# main.net
KiCad netlist of a schematic drawn in EAGLE
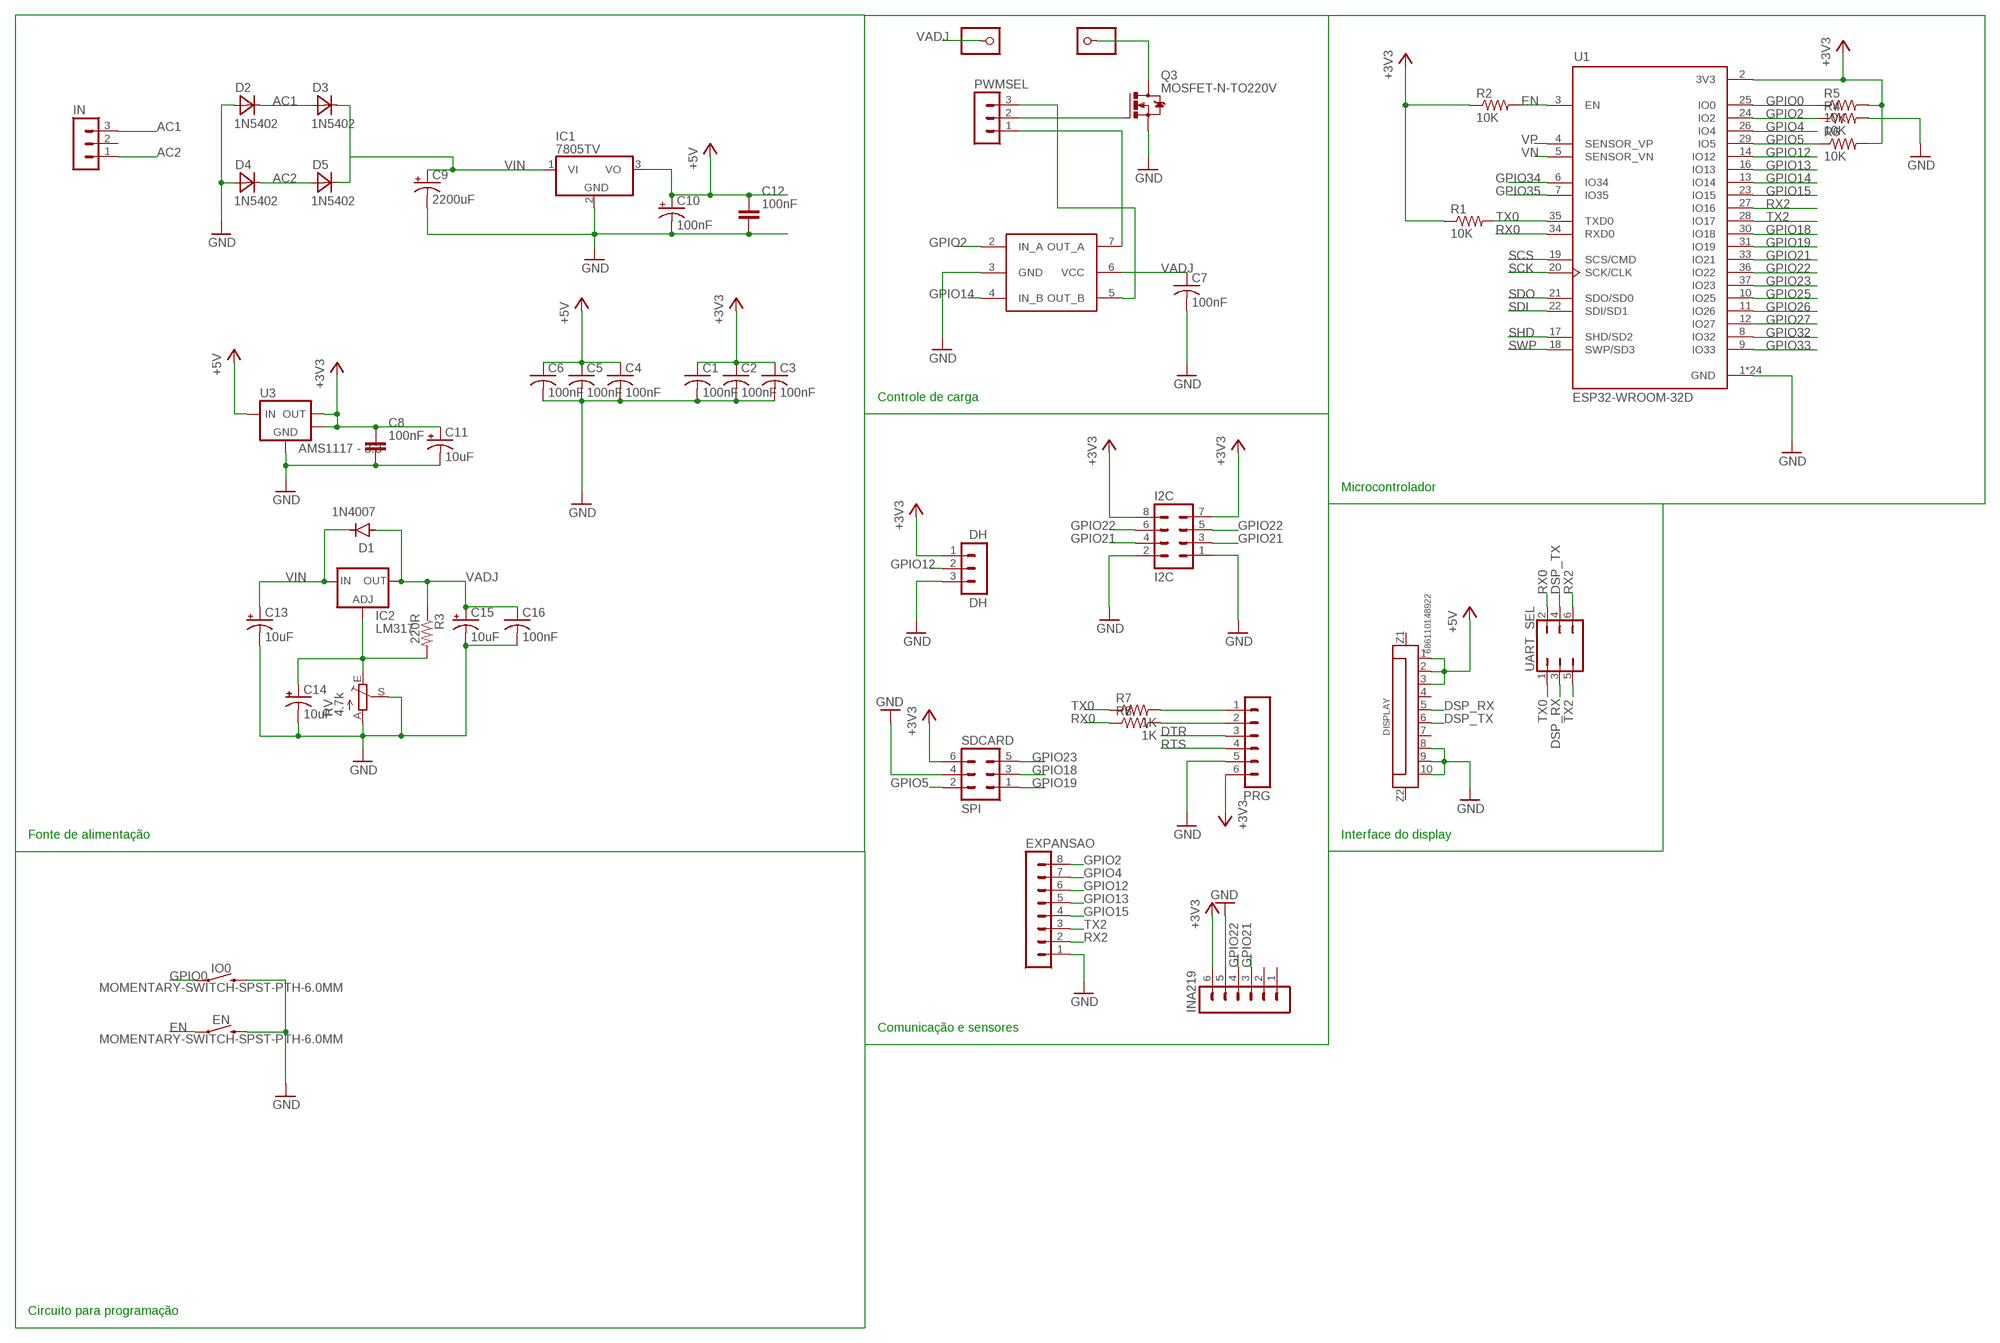
[diagram p0: schematic, sheet 1]

(export (version "E")
  (design (tool "Eeschema 10.0.6"))
  (components
    (comp (ref "C1")
      (value "100nF")
      (footprint "eagle-import:C0805K")
      (libsource (lib "eagle-import") (part "C-USC0805K"))
    )
    (comp (ref "C2")
      (value "100nF")
      (footprint "eagle-import:C0805K")
      (libsource (lib "eagle-import") (part "C-USC0805K"))
    )
    (comp (ref "C3")
      (value "100nF")
      (footprint "eagle-import:C0805K")
      (libsource (lib "eagle-import") (part "C-USC0805K"))
    )
    (comp (ref "C4")
      (value "100nF")
      (footprint "eagle-import:C0805K")
      (libsource (lib "eagle-import") (part "C-USC0805K"))
    )
    (comp (ref "C5")
      (value "100nF")
      (footprint "eagle-import:C0805K")
      (libsource (lib "eagle-import") (part "C-USC0805K"))
    )
    (comp (ref "C6")
      (value "100nF")
      (footprint "eagle-import:C0805K")
      (libsource (lib "eagle-import") (part "C-USC0805K"))
    )
    (comp (ref "C7")
      (value "100nF")
      (footprint "eagle-import:C0805K")
      (libsource (lib "eagle-import") (part "C-USC0805K"))
    )
    (comp (ref "C8")
      (value "100nF")
      (footprint "eagle-import:CAPC2012X110")
      (libsource (lib "eagle-import") (part "CCHIP-0805(2012-METRIC)_"))
    )
    (comp (ref "C9")
      (value "2200uF")
      (footprint "eagle-import:E5-6")
      (libsource (lib "eagle-import") (part "CPOL-5-6MM"))
    )
    (comp (ref "C10")
      (value "100nF")
      (footprint "eagle-import:E2,5-5")
      (libsource (lib "eagle-import") (part "CPOL-2.54-5MM"))
    )
    (comp (ref "C11")
      (value "10uF")
      (footprint "eagle-import:E2,5-5")
      (libsource (lib "eagle-import") (part "CPOL-2.54-5MM"))
    )
    (comp (ref "C12")
      (value "100nF")
      (footprint "eagle-import:CAPC2012X110")
      (libsource (lib "eagle-import") (part "CCHIP-0805(2012-METRIC)_"))
    )
    (comp (ref "C13")
      (value "10uF")
      (footprint "eagle-import:E2-4")
      (libsource (lib "eagle-import") (part "CPOL-USE2-4"))
    )
    (comp (ref "C14")
      (value "10uF")
      (footprint "eagle-import:E2-4")
      (libsource (lib "eagle-import") (part "CPOL-USE2-4"))
    )
    (comp (ref "C15")
      (value "10uF")
      (footprint "eagle-import:E2,5-5")
      (libsource (lib "eagle-import") (part "CPOL-USE2.5-5"))
    )
    (comp (ref "C16")
      (value "100nF")
      (footprint "eagle-import:C0805K")
      (libsource (lib "eagle-import") (part "C-USC0805K"))
    )
    (comp (ref "D1")
      (value "1N4007")
      (footprint "eagle-import:DO-41")
      (fields
        (field (name "DIGIKEY_PART_NUMBER") "1N4007MSCT-ND")
        (field (name "MANUFACTURER") "Micro Commercial Co")
        (field (name "CREATED_BY") "PCBLayout.com")
      )
      (libsource (lib "eagle-import") (part "1N4007"))
    )
    (comp (ref "D2")
      (value "1N5402")
      (footprint "eagle-import:DO201")
      (fields (field (name "MF") "Diodes Inc.") (field (name "MP") "1N5402-T"))
      (libsource (lib "eagle-import") (part "1N5402"))
    )
    (comp (ref "D3")
      (value "1N5402")
      (footprint "eagle-import:DO201")
      (fields (field (name "MF") "Diodes Inc.") (field (name "MP") "1N5402-T"))
      (libsource (lib "eagle-import") (part "1N5402"))
    )
    (comp (ref "D4")
      (value "1N5402")
      (footprint "eagle-import:DO201")
      (fields (field (name "MF") "Diodes Inc.") (field (name "MP") "1N5402-T"))
      (libsource (lib "eagle-import") (part "1N5402"))
    )
    (comp (ref "D5")
      (value "1N5402")
      (footprint "eagle-import:DO201")
      (fields (field (name "MF") "Diodes Inc.") (field (name "MP") "1N5402-T"))
      (libsource (lib "eagle-import") (part "1N5402"))
    )
    (comp (ref "DH")
      (value "DH")
      (footprint "eagle-import:MA03-1")
      (libsource (lib "eagle-import") (part "MA03-1"))
    )
    (comp (ref "DISPLAY")
      (value "686110148922")
      (footprint "eagle-import:686110148922")
      (libsource (lib "eagle-import") (part "6861XX148922_686110148922"))
    )
    (comp (ref "EN")
      (value "MOMENTARY-SWITCH-SPST-PTH-6.0MM")
      (footprint "eagle-import:TACTILE_SWITCH_PTH_6.0MM")
      (libsource (lib "eagle-import") (part "MOMENTARY-SWITCH-SPST-PTH-6.0MM"))
    )
    (comp (ref "EXPANSAO")
      (value "MA08-1")
      (footprint "eagle-import:MA08-1")
      (libsource (lib "eagle-import") (part "MA08-1"))
    )
    (comp (ref "I2C")
      (value "I2C")
      (footprint "eagle-import:MA04-2")
      (libsource (lib "eagle-import") (part "MA04-2"))
    )
    (comp (ref "IC1")
      (value "7805TV")
      (footprint "eagle-import:TO220V")
      (libsource (lib "eagle-import") (part "78TV05"))
    )
    (comp (ref "IC2")
      (value "LM317")
      (footprint "eagle-import:317TS")
      (libsource (lib "eagle-import") (part "LM317TS"))
    )
    (comp (ref "IN")
      (value "MA03-1")
      (footprint "eagle-import:MA03-1")
      (libsource (lib "eagle-import") (part "MA03-1"))
    )
    (comp (ref "INA219")
      (value "MA06-1")
      (footprint "eagle-import:MA06-1")
      (libsource (lib "eagle-import") (part "MA06-1"))
    )
    (comp (ref "IO0")
      (value "MOMENTARY-SWITCH-SPST-PTH-6.0MM")
      (footprint "eagle-import:TACTILE_SWITCH_PTH_6.0MM")
      (libsource (lib "eagle-import") (part "MOMENTARY-SWITCH-SPST-PTH-6.0MM"))
    )
    (comp (ref "JP1")
      (value "PINHD-1X01_2.54-S")
      (footprint "eagle-import:1X01-S")
      (libsource (lib "eagle-import") (part "PINHD-1X01_2.54-S"))
    )
    (comp (ref "LOAD")
      (value "PINHD-1X01_2.54-S")
      (footprint "eagle-import:1X01-S")
      (libsource (lib "eagle-import") (part "PINHD-1X01_2.54-S"))
    )
    (comp (ref "PRG")
      (value "MA06-1")
      (footprint "eagle-import:MA06-1")
      (libsource (lib "eagle-import") (part "MA06-1"))
    )
    (comp (ref "PWMSEL")
      (value "MA03-1")
      (footprint "eagle-import:MA03-1")
      (libsource (lib "eagle-import") (part "MA03-1"))
    )
    (comp (ref "Q3")
      (value "MOSFET-N-TO220V")
      (footprint "eagle-import:TO220BV")
      (libsource (lib "eagle-import") (part "MOSFET-N-TO220V"))
    )
    (comp (ref "R1")
      (value "10K")
      (footprint "eagle-import:M0805")
      (libsource (lib "eagle-import") (part "R-US_M0805"))
    )
    (comp (ref "R2")
      (value "10K")
      (footprint "eagle-import:M0805")
      (libsource (lib "eagle-import") (part "R-US_M0805"))
    )
    (comp (ref "R3")
      (value "220R")
      (footprint "eagle-import:0207_5V")
      (libsource (lib "eagle-import") (part "R0207V-PTH"))
    )
    (comp (ref "R4")
      (value "10K")
      (footprint "eagle-import:M0805")
      (libsource (lib "eagle-import") (part "R-US_M0805"))
    )
    (comp (ref "R5")
      (value "10K")
      (footprint "eagle-import:M0805")
      (libsource (lib "eagle-import") (part "R-US_M0805"))
    )
    (comp (ref "R6")
      (value "10K")
      (footprint "eagle-import:M0805")
      (libsource (lib "eagle-import") (part "R-US_M0805"))
    )
    (comp (ref "R7")
      (value "1K")
      (footprint "eagle-import:M0805")
      (libsource (lib "eagle-import") (part "R-US_M0805"))
    )
    (comp (ref "R8")
      (value "1K")
      (footprint "eagle-import:M0805")
      (libsource (lib "eagle-import") (part "R-US_M0805"))
    )
    (comp (ref "RV")
      (value "4.7k")
      (footprint "eagle-import:RJ9W")
      (libsource (lib "eagle-import") (part "TRIM_EU-RJ9W"))
    )
    (comp (ref "SDCARD")
      (value "SPI")
      (footprint "eagle-import:MA03-2")
      (libsource (lib "eagle-import") (part "MA03-2"))
    )
    (comp (ref "U1")
      (value "ESP32-WROOM-32D")
      (footprint "eagle-import:MODULE_ESP32-WROOM-32D")
      (fields (field (name "MF") "Espressif Systems"))
      (libsource (lib "eagle-import") (part "ESP32-WROOM-32D"))
    )
    (comp (ref "U2")
      (value "MC34151")
      (footprint "eagle-import:DIL8")
      (libsource (lib "eagle-import") (part "MC34151"))
    )
    (comp (ref "U3")
      (value "AMS1117 - 3.3")
      (footprint "eagle-import:SOT-223-3")
      (libsource (lib "eagle-import") (part "LM1117-SOT223"))
    )
    (comp (ref "UART_SEL")
      (value "JP3Q")
      (footprint "eagle-import:JP3Q")
      (libsource (lib "eagle-import") (part "JP3Q"))
    )
  )
  (nets
    (net (code "1") (name "+3V3") (class "Default")
      (node (ref "C1") (pin "1") (pinfunction "1_1") (pintype "passive"))
      (node (ref "C11") (pin "+") (pinfunction "+_+") (pintype "passive"))
      (node (ref "C2") (pin "1") (pinfunction "1_1") (pintype "passive"))
      (node (ref "C3") (pin "1") (pinfunction "1_1") (pintype "passive"))
      (node (ref "C8") (pin "1") (pinfunction "1_1") (pintype "passive"))
      (node (ref "DH") (pin "1") (pinfunction "1_1") (pintype "passive"))
      (node (ref "I2C") (pin "7") (pinfunction "7_7") (pintype "passive"))
      (node (ref "I2C") (pin "8") (pinfunction "8_8") (pintype "passive"))
      (node (ref "INA219") (pin "6") (pinfunction "6_6") (pintype "passive"))
      (node (ref "PRG") (pin "6") (pinfunction "6_6") (pintype "passive"))
      (node (ref "R1") (pin "1") (pinfunction "1_1") (pintype "passive"))
      (node (ref "R2") (pin "1") (pinfunction "1_1") (pintype "passive"))
      (node (ref "R5") (pin "2") (pinfunction "2_2") (pintype "passive"))
      (node (ref "R6") (pin "2") (pinfunction "2_2") (pintype "passive"))
      (node (ref "SDCARD") (pin "6") (pinfunction "6_6") (pintype "passive"))
      (node (ref "U1") (pin "2") (pinfunction "3V3_2") (pintype "power_in"))
      (node (ref "U3") (pin "2") (pinfunction "VOUT_2") (pintype "power_in"))
      (node (ref "U3") (pin "4") (pinfunction "HEATSINK_4") (pintype "power_in"))
    )
    (net (code "2") (name "+5V") (class "Default")
      (node (ref "C10") (pin "+") (pinfunction "+_+") (pintype "passive"))
      (node (ref "C12") (pin "1") (pinfunction "1_1") (pintype "passive"))
      (node (ref "C4") (pin "1") (pinfunction "1_1") (pintype "passive"))
      (node (ref "C5") (pin "1") (pinfunction "1_1") (pintype "passive"))
      (node (ref "C6") (pin "1") (pinfunction "1_1") (pintype "passive"))
      (node (ref "DISPLAY") (pin "1") (pinfunction "1_1") (pintype "passive"))
      (node (ref "DISPLAY") (pin "2") (pinfunction "2_2") (pintype "passive"))
      (node (ref "DISPLAY") (pin "3") (pinfunction "3_3") (pintype "passive"))
      (node (ref "IC1") (pin "3") (pinfunction "VO_3") (pintype "passive"))
      (node (ref "U3") (pin "3") (pinfunction "VIN_3") (pintype "power_in"))
    )
    (net (code "3") (name "/AC1") (class "Default")
      (node (ref "D2") (pin "C") (pinfunction "C_C") (pintype "passive"))
      (node (ref "D3") (pin "A") (pinfunction "A_A") (pintype "passive"))
      (node (ref "IN") (pin "3") (pinfunction "3_3") (pintype "passive"))
    )
    (net (code "4") (name "/AC2") (class "Default")
      (node (ref "D4") (pin "C") (pinfunction "C_C") (pintype "passive"))
      (node (ref "D5") (pin "A") (pinfunction "A_A") (pintype "passive"))
      (node (ref "IN") (pin "1") (pinfunction "1_1") (pintype "passive"))
    )
    (net (code "5") (name "/DSP_RX") (class "Default")
      (node (ref "DISPLAY") (pin "5") (pinfunction "5_5") (pintype "passive"))
      (node (ref "UART_SEL") (pin "3") (pinfunction "3_3") (pintype "passive"))
    )
    (net (code "6") (name "/DSP_TX") (class "Default")
      (node (ref "DISPLAY") (pin "6") (pinfunction "6_6") (pintype "passive"))
      (node (ref "UART_SEL") (pin "4") (pinfunction "4_4") (pintype "passive"))
    )
    (net (code "7") (name "/DTR") (class "Default")
      (node (ref "PRG") (pin "3") (pinfunction "3_3") (pintype "passive"))
    )
    (net (code "8") (name "/EN") (class "Default")
      (node (ref "EN") (pin "1") (pinfunction "1_1") (pintype "passive"))
      (node (ref "R2") (pin "2") (pinfunction "2_2") (pintype "passive"))
      (node (ref "U1") (pin "3") (pinfunction "EN_3") (pintype "input"))
    )
    (net (code "9") (name "/GPIO0") (class "Default")
      (node (ref "IO0") (pin "1") (pinfunction "1_1") (pintype "passive"))
      (node (ref "R5") (pin "1") (pinfunction "1_1") (pintype "passive"))
      (node (ref "U1") (pin "25") (pinfunction "IO0_25") (pintype "bidirectional"))
    )
    (net (code "10") (name "/GPIO2") (class "Default")
      (node (ref "EXPANSAO") (pin "8") (pinfunction "8_8") (pintype "passive"))
      (node (ref "R4") (pin "1") (pinfunction "1_1") (pintype "passive"))
      (node (ref "U1") (pin "24") (pinfunction "IO2_24") (pintype "bidirectional"))
      (node (ref "U2") (pin "2") (pinfunction "IN_A_2") (pintype "bidirectional"))
    )
    (net (code "11") (name "/GPIO4") (class "Default")
      (node (ref "EXPANSAO") (pin "7") (pinfunction "7_7") (pintype "passive"))
      (node (ref "U1") (pin "26") (pinfunction "IO4_26") (pintype "bidirectional"))
    )
    (net (code "12") (name "/GPIO5") (class "Default")
      (node (ref "R6") (pin "1") (pinfunction "1_1") (pintype "passive"))
      (node (ref "SDCARD") (pin "2") (pinfunction "2_2") (pintype "passive"))
      (node (ref "U1") (pin "29") (pinfunction "IO5_29") (pintype "bidirectional"))
    )
    (net (code "13") (name "/GPIO12") (class "Default")
      (node (ref "DH") (pin "2") (pinfunction "2_2") (pintype "passive"))
      (node (ref "EXPANSAO") (pin "6") (pinfunction "6_6") (pintype "passive"))
      (node (ref "U1") (pin "14") (pinfunction "IO12_14") (pintype "bidirectional"))
    )
    (net (code "14") (name "/GPIO13") (class "Default")
      (node (ref "EXPANSAO") (pin "5") (pinfunction "5_5") (pintype "passive"))
      (node (ref "U1") (pin "16") (pinfunction "IO13_16") (pintype "bidirectional"))
    )
    (net (code "15") (name "/GPIO14") (class "Default")
      (node (ref "U1") (pin "13") (pinfunction "IO14_13") (pintype "bidirectional"))
      (node (ref "U2") (pin "4") (pinfunction "IN_B_4") (pintype "bidirectional"))
    )
    (net (code "16") (name "/GPIO15") (class "Default")
      (node (ref "EXPANSAO") (pin "4") (pinfunction "4_4") (pintype "passive"))
      (node (ref "U1") (pin "23") (pinfunction "IO15_23") (pintype "bidirectional"))
    )
    (net (code "17") (name "/GPIO18") (class "Default")
      (node (ref "SDCARD") (pin "3") (pinfunction "3_3") (pintype "passive"))
      (node (ref "U1") (pin "30") (pinfunction "IO18_30") (pintype "bidirectional"))
    )
    (net (code "18") (name "/GPIO19") (class "Default")
      (node (ref "SDCARD") (pin "1") (pinfunction "1_1") (pintype "passive"))
      (node (ref "U1") (pin "31") (pinfunction "IO19_31") (pintype "bidirectional"))
    )
    (net (code "19") (name "/GPIO21") (class "Default")
      (node (ref "I2C") (pin "3") (pinfunction "3_3") (pintype "passive"))
      (node (ref "I2C") (pin "4") (pinfunction "4_4") (pintype "passive"))
      (node (ref "INA219") (pin "3") (pinfunction "3_3") (pintype "passive"))
      (node (ref "U1") (pin "33") (pinfunction "IO21_33") (pintype "bidirectional"))
    )
    (net (code "20") (name "/GPIO22") (class "Default")
      (node (ref "I2C") (pin "5") (pinfunction "5_5") (pintype "passive"))
      (node (ref "I2C") (pin "6") (pinfunction "6_6") (pintype "passive"))
      (node (ref "INA219") (pin "4") (pinfunction "4_4") (pintype "passive"))
      (node (ref "U1") (pin "36") (pinfunction "IO22_36") (pintype "bidirectional"))
    )
    (net (code "21") (name "/GPIO23") (class "Default")
      (node (ref "SDCARD") (pin "5") (pinfunction "5_5") (pintype "passive"))
      (node (ref "U1") (pin "37") (pinfunction "IO23_37") (pintype "bidirectional"))
    )
    (net (code "22") (name "/GPIO25") (class "Default")
      (node (ref "U1") (pin "10") (pinfunction "IO25_10") (pintype "bidirectional"))
    )
    (net (code "23") (name "/GPIO26") (class "Default")
      (node (ref "U1") (pin "11") (pinfunction "IO26_11") (pintype "bidirectional"))
    )
    (net (code "24") (name "/GPIO27") (class "Default")
      (node (ref "U1") (pin "12") (pinfunction "IO27_12") (pintype "bidirectional"))
    )
    (net (code "25") (name "/GPIO32") (class "Default")
      (node (ref "U1") (pin "8") (pinfunction "IO32_8") (pintype "bidirectional"))
    )
    (net (code "26") (name "/GPIO33") (class "Default")
      (node (ref "U1") (pin "9") (pinfunction "IO33_9") (pintype "bidirectional"))
    )
    (net (code "27") (name "/GPIO34") (class "Default")
      (node (ref "U1") (pin "6") (pinfunction "IO34_6") (pintype "input"))
    )
    (net (code "28") (name "/GPIO35") (class "Default")
      (node (ref "U1") (pin "7") (pinfunction "IO35_7") (pintype "input"))
    )
    (net (code "29") (name "/RTS") (class "Default")
      (node (ref "PRG") (pin "4") (pinfunction "4_4") (pintype "passive"))
    )
    (net (code "30") (name "/RX0") (class "Default")
      (node (ref "R8") (pin "1") (pinfunction "1_1") (pintype "passive"))
      (node (ref "U1") (pin "34") (pinfunction "RXD0_34") (pintype "bidirectional"))
      (node (ref "UART_SEL") (pin "2") (pinfunction "2_2") (pintype "passive"))
    )
    (net (code "31") (name "/RX2") (class "Default")
      (node (ref "EXPANSAO") (pin "2") (pinfunction "2_2") (pintype "passive"))
      (node (ref "U1") (pin "27") (pinfunction "IO16_27") (pintype "bidirectional"))
      (node (ref "UART_SEL") (pin "6") (pinfunction "6_6") (pintype "passive"))
    )
    (net (code "32") (name "/SCK") (class "Default")
      (node (ref "U1") (pin "20") (pinfunction "SCK/CLK_20") (pintype "bidirectional"))
    )
    (net (code "33") (name "/SCS") (class "Default")
      (node (ref "U1") (pin "19") (pinfunction "SCS/CMD_19") (pintype "bidirectional"))
    )
    (net (code "34") (name "/SDI") (class "Default")
      (node (ref "U1") (pin "22") (pinfunction "SDI/SD1_22") (pintype "bidirectional"))
    )
    (net (code "35") (name "/SDO") (class "Default")
      (node (ref "U1") (pin "21") (pinfunction "SDO/SD0_21") (pintype "bidirectional"))
    )
    (net (code "36") (name "/SHD") (class "Default")
      (node (ref "U1") (pin "17") (pinfunction "SHD/SD2_17") (pintype "bidirectional"))
    )
    (net (code "37") (name "/SWP") (class "Default")
      (node (ref "U1") (pin "18") (pinfunction "SWP/SD3_18") (pintype "bidirectional"))
    )
    (net (code "38") (name "/TX0") (class "Default")
      (node (ref "R1") (pin "2") (pinfunction "2_2") (pintype "passive"))
      (node (ref "R7") (pin "1") (pinfunction "1_1") (pintype "passive"))
      (node (ref "U1") (pin "35") (pinfunction "TXD0_35") (pintype "bidirectional"))
      (node (ref "UART_SEL") (pin "1") (pinfunction "1_1") (pintype "passive"))
    )
    (net (code "39") (name "/TX2") (class "Default")
      (node (ref "EXPANSAO") (pin "3") (pinfunction "3_3") (pintype "passive"))
      (node (ref "U1") (pin "28") (pinfunction "IO17_28") (pintype "bidirectional"))
      (node (ref "UART_SEL") (pin "5") (pinfunction "5_5") (pintype "passive"))
    )
    (net (code "40") (name "/VADJ") (class "Default")
      (node (ref "C15") (pin "+") (pinfunction "+_+") (pintype "passive"))
      (node (ref "C16") (pin "1") (pinfunction "1_1") (pintype "passive"))
      (node (ref "C7") (pin "1") (pinfunction "1_1") (pintype "passive"))
      (node (ref "D1") (pin "A") (pinfunction "A_A") (pintype "passive"))
      (node (ref "IC2") (pin "2") (pinfunction "OUT_2") (pintype "passive"))
      (node (ref "JP1") (pin "1") (pinfunction "1_1") (pintype "passive"))
      (node (ref "R3") (pin "1") (pinfunction "1_1") (pintype "passive"))
      (node (ref "U2") (pin "6") (pinfunction "VCC_6") (pintype "bidirectional"))
    )
    (net (code "41") (name "/VIN") (class "Default")
      (node (ref "C13") (pin "+") (pinfunction "+_+") (pintype "passive"))
      (node (ref "C9") (pin "+") (pinfunction "+_+") (pintype "passive"))
      (node (ref "D1") (pin "C") (pinfunction "C_C") (pintype "passive"))
      (node (ref "D3") (pin "C") (pinfunction "C_C") (pintype "passive"))
      (node (ref "D5") (pin "C") (pinfunction "C_C") (pintype "passive"))
      (node (ref "IC1") (pin "1") (pinfunction "VI_1") (pintype "input"))
      (node (ref "IC2") (pin "3") (pinfunction "IN_3") (pintype "input"))
    )
    (net (code "42") (name "/VN") (class "Default")
      (node (ref "U1") (pin "5") (pinfunction "SENSOR_VN_5") (pintype "input"))
    )
    (net (code "43") (name "/VP") (class "Default")
      (node (ref "U1") (pin "4") (pinfunction "SENSOR_VP_4") (pintype "input"))
    )
    (net (code "44") (name "GND") (class "Default")
      (node (ref "C1") (pin "2") (pinfunction "2_2") (pintype "passive"))
      (node (ref "C10") (pin "-") (pinfunction "-_-") (pintype "passive"))
      (node (ref "C11") (pin "-") (pinfunction "-_-") (pintype "passive"))
      (node (ref "C12") (pin "2") (pinfunction "2_2") (pintype "passive"))
      (node (ref "C13") (pin "-") (pinfunction "-_-") (pintype "passive"))
      (node (ref "C14") (pin "-") (pinfunction "-_-") (pintype "passive"))
      (node (ref "C15") (pin "-") (pinfunction "-_-") (pintype "passive"))
      (node (ref "C16") (pin "2") (pinfunction "2_2") (pintype "passive"))
      (node (ref "C2") (pin "2") (pinfunction "2_2") (pintype "passive"))
      (node (ref "C3") (pin "2") (pinfunction "2_2") (pintype "passive"))
      (node (ref "C4") (pin "2") (pinfunction "2_2") (pintype "passive"))
      (node (ref "C5") (pin "2") (pinfunction "2_2") (pintype "passive"))
      (node (ref "C6") (pin "2") (pinfunction "2_2") (pintype "passive"))
      (node (ref "C7") (pin "2") (pinfunction "2_2") (pintype "passive"))
      (node (ref "C8") (pin "2") (pinfunction "2_2") (pintype "passive"))
      (node (ref "C9") (pin "-") (pinfunction "-_-") (pintype "passive"))
      (node (ref "D2") (pin "A") (pinfunction "A_A") (pintype "passive"))
      (node (ref "D4") (pin "A") (pinfunction "A_A") (pintype "passive"))
      (node (ref "DH") (pin "3") (pinfunction "3_3") (pintype "passive"))
      (node (ref "DISPLAY") (pin "10") (pinfunction "10_10") (pintype "passive"))
      (node (ref "DISPLAY") (pin "8") (pinfunction "8_8") (pintype "passive"))
      (node (ref "DISPLAY") (pin "9") (pinfunction "9_9") (pintype "passive"))
      (node (ref "EN") (pin "3") (pinfunction "2_3") (pintype "passive"))
      (node (ref "EXPANSAO") (pin "1") (pinfunction "1_1") (pintype "passive"))
      (node (ref "I2C") (pin "1") (pinfunction "1_1") (pintype "passive"))
      (node (ref "I2C") (pin "2") (pinfunction "2_2") (pintype "passive"))
      (node (ref "IC1") (pin "2") (pinfunction "GND_2") (pintype "passive"))
      (node (ref "INA219") (pin "5") (pinfunction "5_5") (pintype "passive"))
      (node (ref "IO0") (pin "3") (pinfunction "2_3") (pintype "passive"))
      (node (ref "PRG") (pin "5") (pinfunction "5_5") (pintype "passive"))
      (node (ref "Q3") (pin "S") (pinfunction "S_S") (pintype "passive"))
      (node (ref "R4") (pin "2") (pinfunction "2_2") (pintype "passive"))
      (node (ref "RV") (pin "A") (pinfunction "A_A") (pintype "passive"))
      (node (ref "RV") (pin "S") (pinfunction "S_S") (pintype "passive"))
      (node (ref "SDCARD") (pin "4") (pinfunction "4_4") (pintype "passive"))
      (node (ref "U1") (pin "1") (pinfunction "GND_1") (pintype "power_in"))
      (node (ref "U1") (pin "15") (pinfunction "GND_15") (pintype "power_in"))
      (node (ref "U1") (pin "38") (pinfunction "GND_38") (pintype "power_in"))
      (node (ref "U1") (pin "39_1") (pinfunction "GND_39_1") (pintype "power_in"))
      (node (ref "U1") (pin "39_10") (pinfunction "GND_39_10") (pintype "power_in"))
      (node (ref "U1") (pin "39_11") (pinfunction "GND_39_11") (pintype "power_in"))
      (node (ref "U1") (pin "39_12") (pinfunction "GND_39_12") (pintype "power_in"))
      (node (ref "U1") (pin "39_13") (pinfunction "GND_39_13") (pintype "power_in"))
      (node (ref "U1") (pin "39_14") (pinfunction "GND_39_14") (pintype "power_in"))
      (node (ref "U1") (pin "39_15") (pinfunction "GND_39_15") (pintype "power_in"))
      (node (ref "U1") (pin "39_16") (pinfunction "GND_39_16") (pintype "power_in"))
      (node (ref "U1") (pin "39_17") (pinfunction "GND_39_17") (pintype "power_in"))
      (node (ref "U1") (pin "39_18") (pinfunction "GND_39_18") (pintype "power_in"))
      (node (ref "U1") (pin "39_19") (pinfunction "GND_39_19") (pintype "power_in"))
      (node (ref "U1") (pin "39_2") (pinfunction "GND_39_2") (pintype "power_in"))
      (node (ref "U1") (pin "39_20") (pinfunction "GND_39_20") (pintype "power_in"))
      (node (ref "U1") (pin "39_21") (pinfunction "GND_39_21") (pintype "power_in"))
      (node (ref "U1") (pin "39_3") (pinfunction "GND_39_3") (pintype "power_in"))
      (node (ref "U1") (pin "39_4") (pinfunction "GND_39_4") (pintype "power_in"))
      (node (ref "U1") (pin "39_5") (pinfunction "GND_39_5") (pintype "power_in"))
      (node (ref "U1") (pin "39_6") (pinfunction "GND_39_6") (pintype "power_in"))
      (node (ref "U1") (pin "39_7") (pinfunction "GND_39_7") (pintype "power_in"))
      (node (ref "U1") (pin "39_8") (pinfunction "GND_39_8") (pintype "power_in"))
      (node (ref "U1") (pin "39_9") (pinfunction "GND_39_9") (pintype "power_in"))
      (node (ref "U2") (pin "3") (pinfunction "GND_3") (pintype "bidirectional"))
      (node (ref "U3") (pin "1") (pinfunction "GND_1") (pintype "power_in"))
    )
    (net (code "45") (name "Net-(IC2-ADJ)") (class "Default")
      (node (ref "C14") (pin "+") (pinfunction "+_+") (pintype "passive"))
      (node (ref "IC2") (pin "1") (pinfunction "ADJ_1") (pintype "input"))
      (node (ref "R3") (pin "2") (pinfunction "2_2") (pintype "passive"))
      (node (ref "RV") (pin "E") (pinfunction "E_E") (pintype "passive"))
    )
    (net (code "46") (name "Net-(LOAD-Pad1)") (class "Default")
      (node (ref "LOAD") (pin "1") (pinfunction "1_1") (pintype "passive"))
      (node (ref "Q3") (pin "D") (pinfunction "D_D") (pintype "passive"))
    )
    (net (code "47") (name "Net-(PRG-Pad1)") (class "Default")
      (node (ref "PRG") (pin "1") (pinfunction "1_1") (pintype "passive"))
      (node (ref "R7") (pin "2") (pinfunction "2_2") (pintype "passive"))
    )
    (net (code "48") (name "Net-(PRG-Pad2)") (class "Default")
      (node (ref "PRG") (pin "2") (pinfunction "2_2") (pintype "passive"))
      (node (ref "R8") (pin "2") (pinfunction "2_2") (pintype "passive"))
    )
    (net (code "49") (name "Net-(PWMSEL-Pad2)") (class "Default")
      (node (ref "PWMSEL") (pin "2") (pinfunction "2_2") (pintype "passive"))
      (node (ref "Q3") (pin "G") (pinfunction "G_G") (pintype "passive"))
    )
    (net (code "50") (name "Net-(U2-OUT_A)") (class "Default")
      (node (ref "PWMSEL") (pin "1") (pinfunction "1_1") (pintype "passive"))
      (node (ref "U2") (pin "7") (pinfunction "OUT_A_7") (pintype "bidirectional"))
    )
    (net (code "51") (name "Net-(U2-OUT_B)") (class "Default")
      (node (ref "PWMSEL") (pin "3") (pinfunction "3_3") (pintype "passive"))
      (node (ref "U2") (pin "5") (pinfunction "OUT_B_5") (pintype "bidirectional"))
    )
    (net (code "52") (name "unconnected-(DISPLAY-Pad4)") (class "Default")
      (node (ref "DISPLAY") (pin "4") (pinfunction "4_4") (pintype "passive"))
    )
    (net (code "53") (name "unconnected-(DISPLAY-Pad7)") (class "Default")
      (node (ref "DISPLAY") (pin "7") (pinfunction "7_7") (pintype "passive"))
    )
    (net (code "54") (name "unconnected-(DISPLAY-PadZ1)") (class "Default")
      (node (ref "DISPLAY") (pin "Z1") (pinfunction "Z1_Z1") (pintype "passive"))
    )
    (net (code "55") (name "unconnected-(DISPLAY-PadZ2)") (class "Default")
      (node (ref "DISPLAY") (pin "Z2") (pinfunction "Z2_Z2") (pintype "passive"))
    )
    (net (code "56") (name "unconnected-(IN-Pad2)") (class "Default")
      (node (ref "IN") (pin "2") (pinfunction "2_2") (pintype "passive"))
    )
    (net (code "57") (name "unconnected-(INA219-Pad1)") (class "Default")
      (node (ref "INA219") (pin "1") (pinfunction "1_1") (pintype "passive"))
    )
    (net (code "58") (name "unconnected-(INA219-Pad2)") (class "Default")
      (node (ref "INA219") (pin "2") (pinfunction "2_2") (pintype "passive"))
    )
  )
)
